# IDX_CTRL.net
KiCad netlist of a schematic drawn in Altium Designer
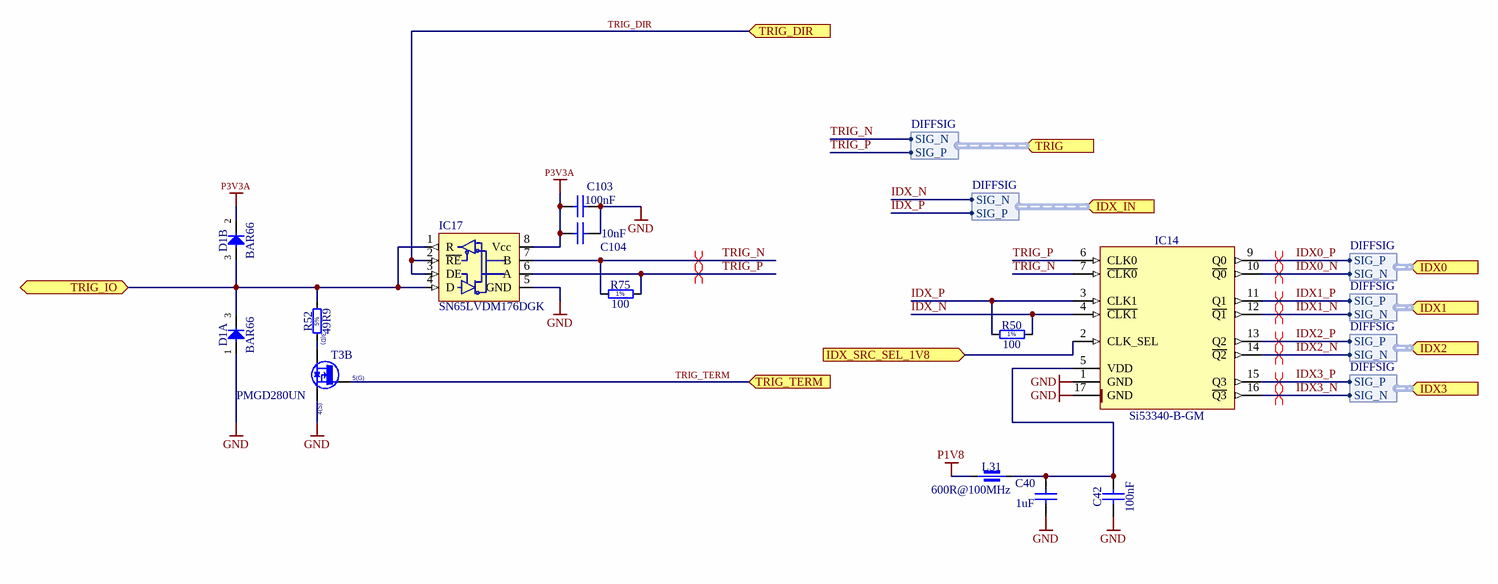
[diagram p0: IDX_CTRL.SchDoc]

(export (version "E")
  (design (tool "Eeschema 10.0.6"))
  (components
    (comp (ref "C40")
      (value "1uF")
      (footprint "CAPC1005X55N")
      (description "Non-polarised capacitor")
      (fields
        (field (name "PART NUMBER") "CC0402_1UF_16V_10%_X5R")
        (field (name "VOLTAGE") "16V")
        (field (name "AUTHOR") "CERN DEM JLC")
      )
      (libsource (lib "Capacitors") (part "Capacitor - non polarized"))
    )
    (comp (ref "C42")
      (value "100nF")
      (footprint "CAPC0603X33N")
      (description "Non-polarised capacitor")
      (fields
        (field (name "PART NUMBER") "CC0201_100NF_6.3V_10%_X5R")
        (field (name "VOLTAGE") "6.3V")
        (field (name "AUTHOR") "CERN DEM JLC")
      )
      (libsource (lib "Capacitors") (part "Capacitor - non polarized"))
    )
    (comp (ref "C103")
      (value "100nF")
      (footprint "CAPC0603X33N")
      (description "Non-polarised capacitor")
      (fields
        (field (name "PART NUMBER") "CC0201_100NF_6.3V_10%_X5R")
        (field (name "VOLTAGE") "6.3V")
        (field (name "AUTHOR") "CERN DEM JLC")
      )
      (libsource (lib "Capacitors") (part "Capacitor - non polarized"))
    )
    (comp (ref "C104")
      (value "10nF")
      (footprint "CAPC0603X33N")
      (description "Non-polarised capacitor")
      (fields
        (field (name "PART NUMBER") "CC0201_10NF_10V_10%_X5R")
        (field (name "VOLTAGE") "10V")
        (field (name "AUTHOR") "CERN DEM JLC")
      )
      (libsource (lib "Capacitors") (part "Capacitor - non polarized"))
    )
    (comp (ref "D1")
      (value "BAR66")
      (footprint "SOT95P240X110-3N")
      (description "Serial Diode")
      (fields
        (field (name "VOLTAGE") "150V")
        (field (name "POWER") "250mA")
        (field (name "AUTHOR") "CERN DEM JLC")
      )
      (libsource (lib "ICs And Semiconductors") (part "Diode x2 A1C3_A3C2"))
    )
    (comp (ref "IC14")
      (value "Si53340-B-GM")
      (footprint "QFN50P300X300X90-17N-S175")
      (description "Low-Jitter LVDS Fanout Clock Buffers, 10-Output,  Any-Input, Any-Frequency up to 1250MHz")
      (fields (field (name "MANUFACTURER") "SILICON LABS") (field (name "AUTHOR") "CERN DEM MR"))
      (libsource (lib "ICs And Semiconductors") (part "Si53340"))
    )
    (comp (ref "IC17")
      (value "SN65LVDM176DGK")
      (footprint "MSOP8 TI/AD")
      (description "High Speed Differential Transceiver LVDS/LVTTL")
      (libsource (lib "Buffers & Drivers") (part "SN65LVDM176"))
    )
    (comp (ref "L31")
      (value "600R@100MHz")
      (footprint "INDC1005X55N")
      (fields
        (field (name "PART NUMBER") "IND0402_MURATA_BLM15HD601SN1")
        (field (name "POWER") "300mA")
        (field (name "TOLERANCE") "±25%")
        (field (name "AUTHOR") "CERN DEM JLC")
      )
      (libsource (lib "Inductors & Transformers") (part "Ferrite Bead"))
    )
    (comp (ref "R50")
      (value "100")
      (footprint "RESC0603X28N")
      (description "Resistor - 1%")
      (fields
        (field (name "PART NUMBER") "R0201_100R_1%_0.05W_200PPM")
        (field (name "POWER") "0.05W")
        (field (name "AUTHOR") "CERN DEM JLC")
      )
      (libsource (lib "Resistors") (part "Resistor - 1%"))
    )
    (comp (ref "R52")
      (value "49R9")
      (footprint "RESC3225X70N")
      (description "Resistor - 5%")
      (fields
        (field (name "PART NUMBER") "R1210_49R9_1%_0.33W_100PPM")
        (field (name "POWER") "0.33W")
        (field (name "AUTHOR") "CERN DEM JLC")
      )
      (libsource (lib "Resistors") (part "Resistor - 5%"))
    )
    (comp (ref "R75")
      (value "100")
      (footprint "RESC0603X28N")
      (description "Resistor - 1%")
      (fields
        (field (name "PART NUMBER") "R0201_100R_1%_0.05W_200PPM")
        (field (name "POWER") "0.05W")
        (field (name "AUTHOR") "CERN DEM JLC")
      )
      (libsource (lib "Resistors") (part "Resistor - 1%"))
    )
    (comp (ref "T3")
      (value "PMGD280UN")
      (footprint "SOT65P210X110-6N")
      (description "Dual N-Channel micro TrenchMOS™ Ultra Low Level FET")
      (fields (field (name "MANUFACTURER") "NXP SEMICONDUCTORS") (field (name "AUTHOR") "CERN DEM JLC"))
      (libsource (lib "ICs And Semiconductors") (part "PMGD280UN"))
    )
  )
  (nets
    (net (code "2") (name "/IDX0_N") (class "Default")
      (node (ref "IC14") (pin "10") (pinfunction "~{Q0}_10") (pintype "output"))
    )
    (net (code "3") (name "/IDX0_P") (class "Default")
      (node (ref "IC14") (pin "9") (pinfunction "Q0_9") (pintype "output"))
    )
    (net (code "4") (name "/IDX1_N") (class "Default")
      (node (ref "IC14") (pin "12") (pinfunction "~{Q1}_12") (pintype "output"))
    )
    (net (code "5") (name "/IDX1_P") (class "Default")
      (node (ref "IC14") (pin "11") (pinfunction "Q1_11") (pintype "output"))
    )
    (net (code "6") (name "/IDX2_N") (class "Default")
      (node (ref "IC14") (pin "14") (pinfunction "~{Q2}_14") (pintype "output"))
    )
    (net (code "7") (name "/IDX2_P") (class "Default")
      (node (ref "IC14") (pin "13") (pinfunction "Q2_13") (pintype "output"))
    )
    (net (code "8") (name "/IDX3_N") (class "Default")
      (node (ref "IC14") (pin "16") (pinfunction "~{Q3}_16") (pintype "output"))
    )
    (net (code "9") (name "/IDX3_P") (class "Default")
      (node (ref "IC14") (pin "15") (pinfunction "Q3_15") (pintype "output"))
    )
    (net (code "10") (name "/IDX_N") (class "Default")
      (node (ref "IC14") (pin "4") (pinfunction "~{CLK1}_4") (pintype "input"))
      (node (ref "R50") (pin "2") (pinfunction "2_2") (pintype "passive"))
    )
    (net (code "11") (name "/IDX_P") (class "Default")
      (node (ref "IC14") (pin "3") (pinfunction "CLK1_3") (pintype "input"))
      (node (ref "R50") (pin "1") (pinfunction "1_1") (pintype "passive"))
    )
    (net (code "12") (name "/IDX_SRC_SEL_1V8") (class "Default")
      (node (ref "IC14") (pin "2") (pinfunction "CLK_SEL_2") (pintype "input"))
    )
    (net (code "13") (name "/TRIG_DIR") (class "Default")
      (node (ref "IC17") (pin "2") (pinfunction "~{RE}_2") (pintype "input"))
      (node (ref "IC17") (pin "3") (pinfunction "DE_3") (pintype "input"))
    )
    (net (code "14") (name "/TRIG_IO") (class "Default")
      (node (ref "D1") (pin "3") (pinfunction "COMAC_3") (pintype "passive"))
      (node (ref "IC17") (pin "1") (pinfunction "R_1") (pintype "output"))
      (node (ref "IC17") (pin "4") (pinfunction "D_4") (pintype "input"))
      (node (ref "R52") (pin "2") (pinfunction "2_2") (pintype "passive"))
    )
    (net (code "15") (name "/TRIG_N") (class "Default")
      (node (ref "IC14") (pin "7") (pinfunction "~{CLK0}_7") (pintype "input"))
      (node (ref "IC17") (pin "7") (pinfunction "B_7") (pintype "bidirectional"))
      (node (ref "R75") (pin "1") (pinfunction "1_1") (pintype "passive"))
    )
    (net (code "16") (name "/TRIG_P") (class "Default")
      (node (ref "IC14") (pin "6") (pinfunction "CLK0_6") (pintype "input"))
      (node (ref "IC17") (pin "6") (pinfunction "A_6") (pintype "bidirectional"))
      (node (ref "R75") (pin "2") (pinfunction "2_2") (pintype "passive"))
    )
    (net (code "17") (name "/TRIG_TERM") (class "Default")
      (node (ref "T3") (pin "5") (pinfunction "G_5") (pintype "passive"))
    )
    (net (code "19") (name "GND") (class "Default")
      (node (ref "C103") (pin "2") (pinfunction "2_2") (pintype "passive"))
      (node (ref "C104") (pin "2") (pinfunction "2_2") (pintype "passive"))
      (node (ref "C40") (pin "1") (pinfunction "1_1") (pintype "passive"))
      (node (ref "C42") (pin "1") (pinfunction "1_1") (pintype "passive"))
      (node (ref "D1") (pin "1") (pinfunction "A_1") (pintype "passive"))
      (node (ref "IC14") (pin "1") (pinfunction "GND_1") (pintype "power_in"))
      (node (ref "IC14") (pin "17") (pinfunction "GND_17") (pintype "power_in"))
      (node (ref "IC17") (pin "5") (pinfunction "GND_5") (pintype "power_in"))
      (node (ref "T3") (pin "4") (pinfunction "S_4") (pintype "passive"))
    )
    (net (code "20") (name "Net-(IC14-VDD)") (class "Default")
      (node (ref "C40") (pin "2") (pinfunction "2_2") (pintype "passive"))
      (node (ref "C42") (pin "2") (pinfunction "2_2") (pintype "passive"))
      (node (ref "IC14") (pin "5") (pinfunction "VDD_5") (pintype "power_in"))
      (node (ref "L31") (pin "2") (pinfunction "2_2") (pintype "passive"))
    )
    (net (code "21") (name "Net-(T3B-D)") (class "Default")
      (node (ref "R52") (pin "1") (pinfunction "1_1") (pintype "passive"))
      (node (ref "T3") (pin "3") (pinfunction "D_3") (pintype "passive"))
    )
    (net (code "22") (name "P1V8") (class "Default")
      (node (ref "L31") (pin "1") (pinfunction "1_1") (pintype "passive"))
    )
    (net (code "23") (name "P3V3A") (class "Default")
      (node (ref "C103") (pin "1") (pinfunction "1_1") (pintype "passive"))
      (node (ref "C104") (pin "1") (pinfunction "1_1") (pintype "passive"))
      (node (ref "D1") (pin "2") (pinfunction "C_2") (pintype "passive"))
      (node (ref "IC17") (pin "8") (pinfunction "Vcc_8") (pintype "power_in"))
    )
  )
)
